# alien.net
KiCad netlist of a schematic drawn in EAGLE
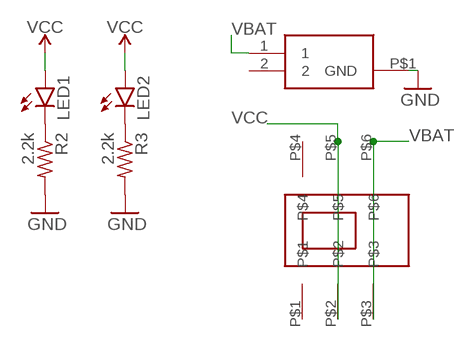
[diagram p0: schematic, sheet 1]

(export (version "E")
  (design (tool "Eeschema 10.0.6"))
  (components
    (comp (ref "LED1")
      (value "LEDCHIP-LED0805")
      (footprint "eagle-import:CHIP-LED0805")
      (libsource (lib "eagle-import") (part "LEDCHIP-LED0805"))
    )
    (comp (ref "LED2")
      (value "LEDCHIP-LED0805")
      (footprint "eagle-import:CHIP-LED0805")
      (libsource (lib "eagle-import") (part "LEDCHIP-LED0805"))
    )
    (comp (ref "R2")
      (value "2.2k")
      (footprint "eagle-import:R0603")
      (libsource (lib "eagle-import") (part "R-US_R0603"))
    )
    (comp (ref "R3")
      (value "2.2k")
      (footprint "eagle-import:R0603")
      (libsource (lib "eagle-import") (part "R-US_R0603"))
    )
    (comp (ref "U$1")
      (value "CL-SB-22A-02T-SLIDE-SWITCH-TUCKED-PADS")
      (footprint "eagle-import:CL-SB-22A-02T-DPDT-COMPACT-SWITCH")
      (libsource (lib "eagle-import") (part "CL-SB-22A-02T-SLIDE-SWITCH-TUCKED-PADS"))
    )
    (comp (ref "VBAT")
      (value "BAT-HLD-012-SMT")
      (footprint "eagle-import:BATHLD012SMT")
      (fields (field (name "MOUSER_PART_NUMBER") "712-BAT-HLD-012-SMT"))
      (libsource (lib "eagle-import") (part "BAT-HLD-012-SMT"))
    )
  )
  (nets
    (net (code "1") (name "/VBAT") (class "Default")
      (node (ref "U$1") (pin "P$3") (pinfunction "P$3_P$3") (pintype "bidirectional"))
      (node (ref "U$1") (pin "P$6") (pinfunction "P$6_P$6") (pintype "bidirectional"))
      (node (ref "VBAT") (pin "1") (pinfunction "1_1") (pintype "bidirectional"))
    )
    (net (code "2") (name "GND") (class "Default")
      (node (ref "R2") (pin "2") (pinfunction "2_2") (pintype "passive"))
      (node (ref "R3") (pin "2") (pinfunction "2_2") (pintype "passive"))
      (node (ref "VBAT") (pin "P$1") (pinfunction "GND_P$1") (pintype "bidirectional"))
    )
    (net (code "3") (name "Net-(LED1-PadC)") (class "Default")
      (node (ref "LED1") (pin "C") (pinfunction "C_C") (pintype "passive"))
      (node (ref "R2") (pin "1") (pinfunction "1_1") (pintype "passive"))
    )
    (net (code "4") (name "Net-(LED2-PadC)") (class "Default")
      (node (ref "LED2") (pin "C") (pinfunction "C_C") (pintype "passive"))
      (node (ref "R3") (pin "1") (pinfunction "1_1") (pintype "passive"))
    )
    (net (code "5") (name "VCC") (class "Default")
      (node (ref "LED1") (pin "A") (pinfunction "A_A") (pintype "passive"))
      (node (ref "LED2") (pin "A") (pinfunction "A_A") (pintype "passive"))
      (node (ref "U$1") (pin "P$2") (pinfunction "P$2_P$2") (pintype "bidirectional"))
      (node (ref "U$1") (pin "P$5") (pinfunction "P$5_P$5") (pintype "bidirectional"))
    )
    (net (code "6") (name "unconnected-(U$1-PadP$1)") (class "Default")
      (node (ref "U$1") (pin "P$1") (pinfunction "P$1_P$1") (pintype "bidirectional"))
    )
    (net (code "7") (name "unconnected-(U$1-PadP$4)") (class "Default")
      (node (ref "U$1") (pin "P$4") (pinfunction "P$4_P$4") (pintype "bidirectional"))
    )
    (net (code "8") (name "unconnected-(VBAT-Pad2)") (class "Default")
      (node (ref "VBAT") (pin "2") (pinfunction "2_2") (pintype "bidirectional"))
    )
  )
)
